# DAC_channel.net
KiCad netlist of a schematic drawn in Altium Designer
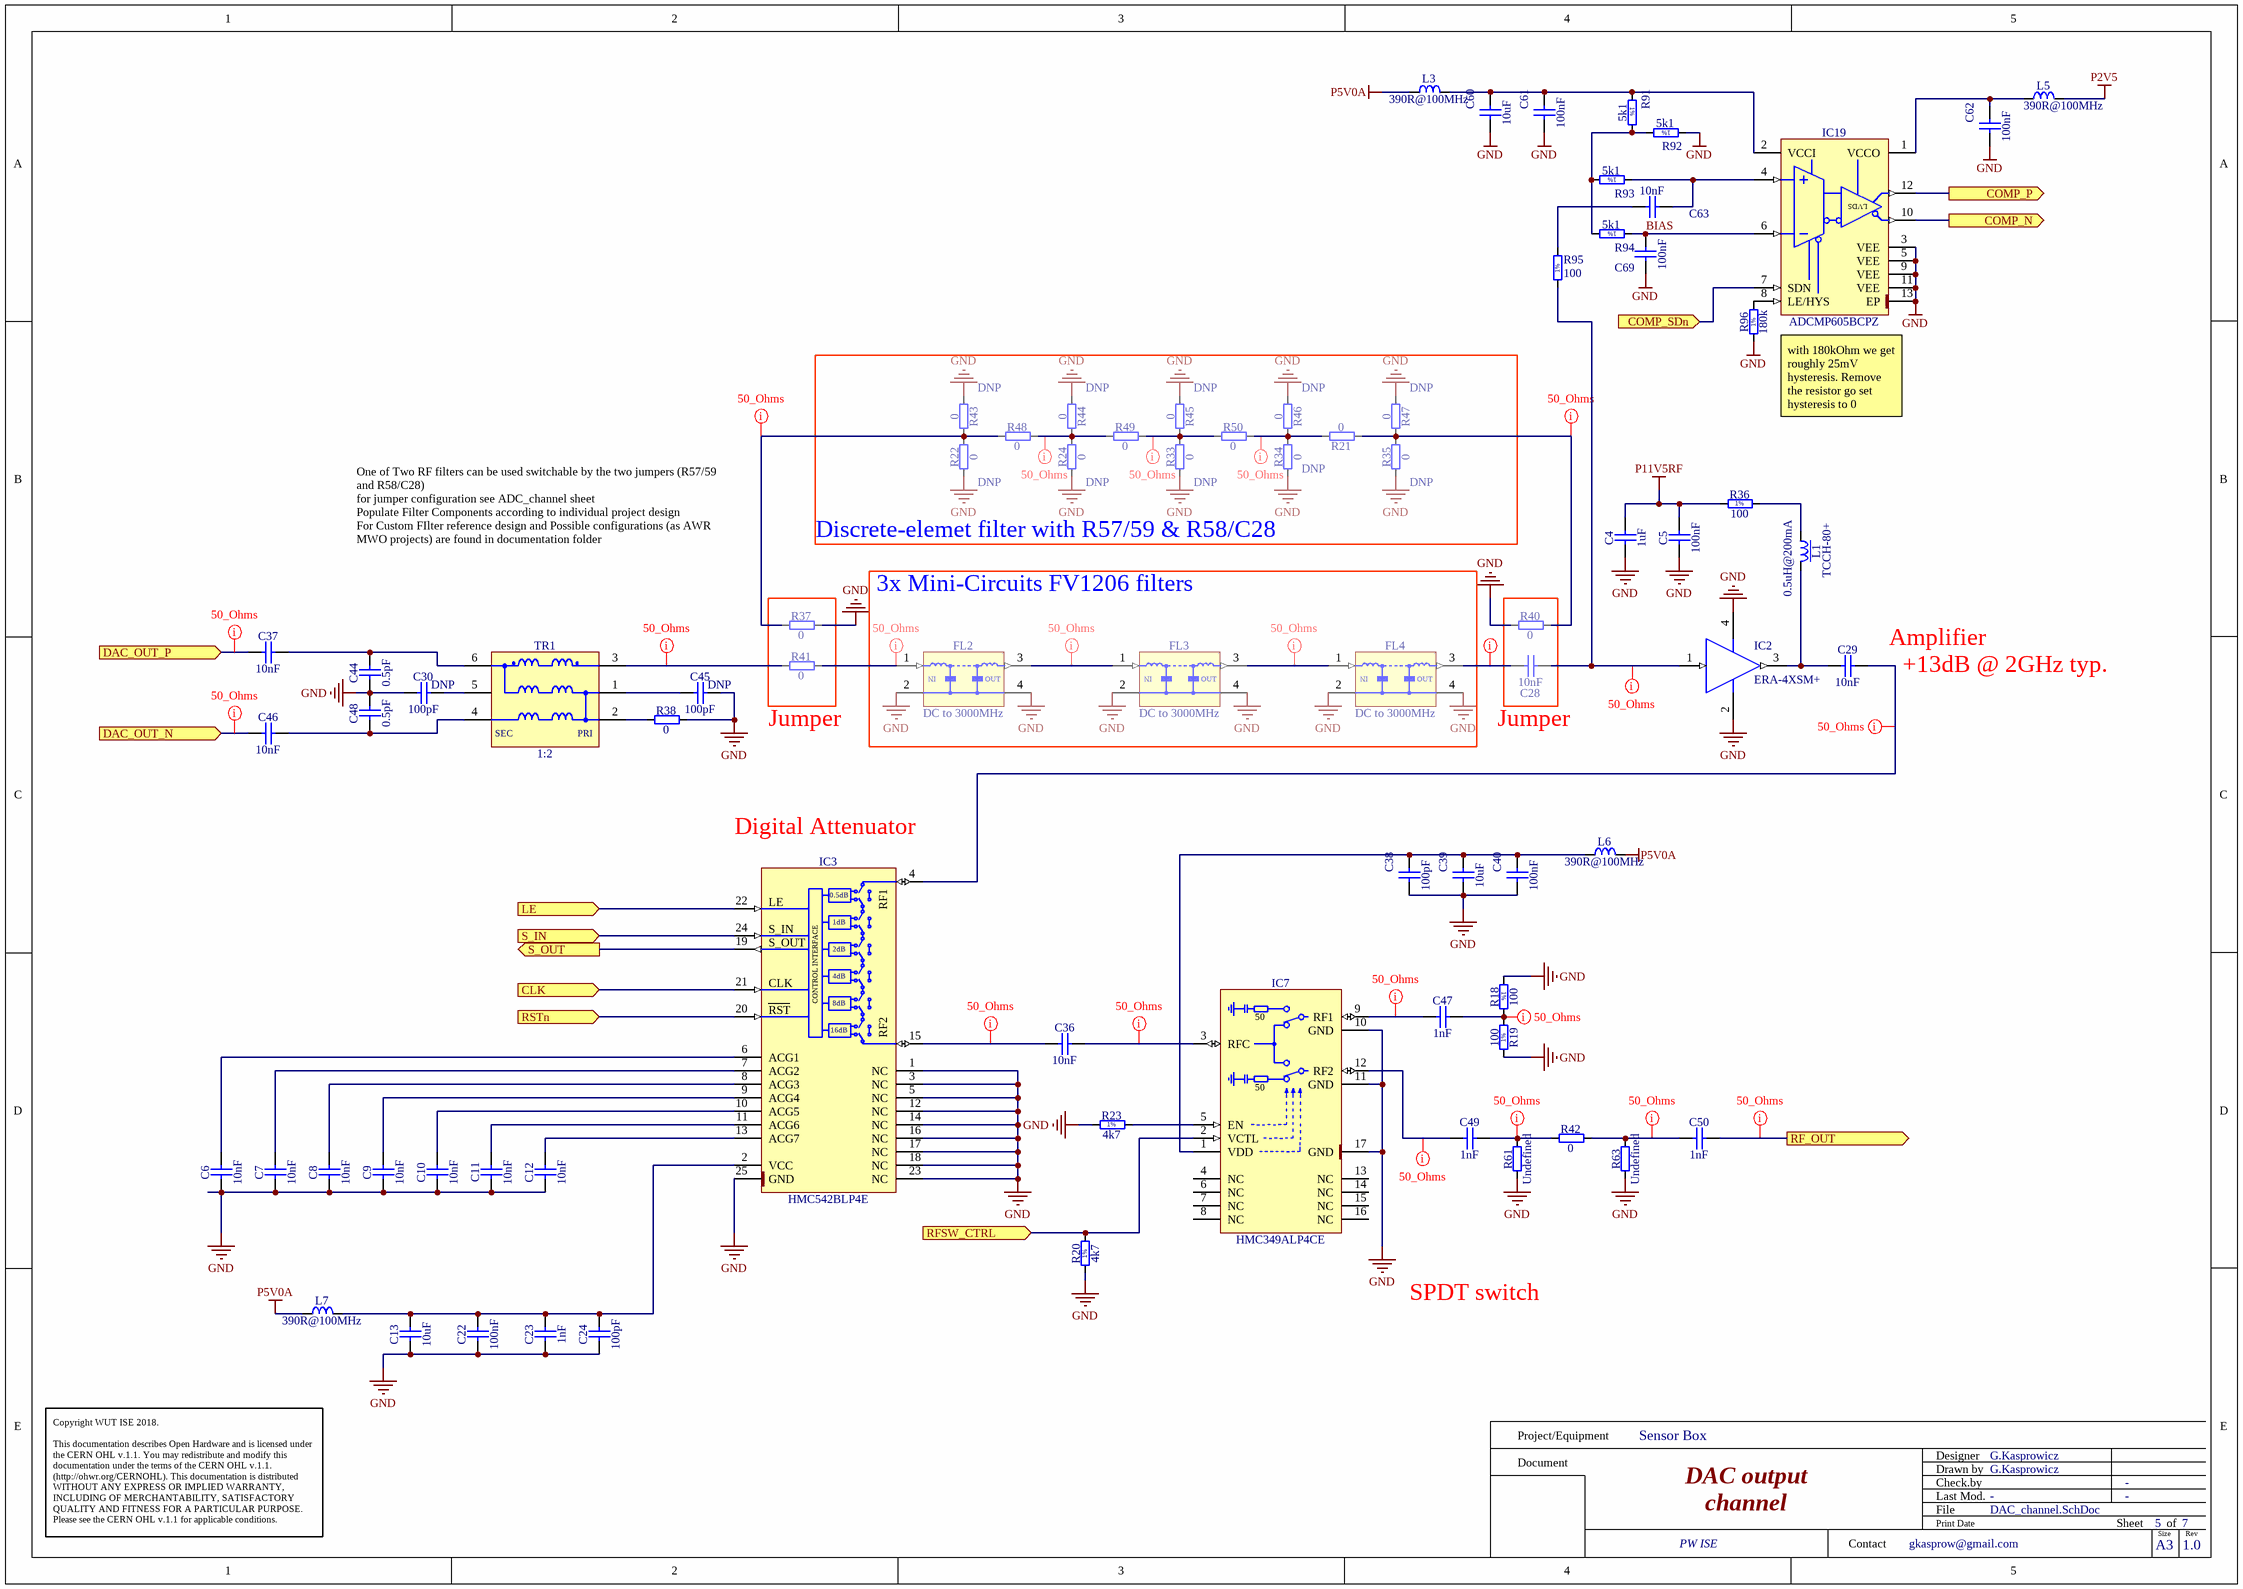
[diagram p0: DAC_channel.SchDoc]

(export (version "E")
  (design (tool "Eeschema 10.0.6"))
  (components
    (comp (ref "C4")
      (value "1uF")
      (footprint "CAPC2012X140N")
      (description "Non-polarised capacitor")
      (fields
        (field (name "PART NUMBER") "CC0805_1UF_35V_20%_X7R")
        (field (name "VOLTAGE") "35V")
        (field (name "AUTHOR") "CERN DEM JLC")
      )
      (libsource (lib "Capacitors") (part "Capacitor - non polarized"))
    )
    (comp (ref "C5")
      (value "100nF")
      (footprint "CAPC1608X87N")
      (description "Non-polarised capacitor")
      (fields
        (field (name "PART NUMBER") "CC0603_100NF_50V_10%_X7R")
        (field (name "VOLTAGE") "50V")
        (field (name "AUTHOR") "CERN DEM JLC")
      )
      (libsource (lib "Capacitors") (part "Capacitor - non polarized"))
    )
    (comp (ref "C6")
      (value "10nF")
      (footprint "CAPC1005X55N")
      (description "Non-polarised capacitor")
      (fields
        (field (name "PART NUMBER") "CC0402_10NF_16V_10%_X7R")
        (field (name "VOLTAGE") "16V")
        (field (name "AUTHOR") "CERN DEM JLC")
      )
      (libsource (lib "Capacitors") (part "Capacitor - non polarized"))
    )
    (comp (ref "C7")
      (value "10nF")
      (footprint "CAPC1005X55N")
      (description "Non-polarised capacitor")
      (fields
        (field (name "PART NUMBER") "CC0402_10NF_16V_10%_X7R")
        (field (name "VOLTAGE") "16V")
        (field (name "AUTHOR") "CERN DEM JLC")
      )
      (libsource (lib "Capacitors") (part "Capacitor - non polarized"))
    )
    (comp (ref "C8")
      (value "10nF")
      (footprint "CAPC1005X55N")
      (description "Non-polarised capacitor")
      (fields
        (field (name "PART NUMBER") "CC0402_10NF_16V_10%_X7R")
        (field (name "VOLTAGE") "16V")
        (field (name "AUTHOR") "CERN DEM JLC")
      )
      (libsource (lib "Capacitors") (part "Capacitor - non polarized"))
    )
    (comp (ref "C9")
      (value "10nF")
      (footprint "CAPC1005X55N")
      (description "Non-polarised capacitor")
      (fields
        (field (name "PART NUMBER") "CC0402_10NF_16V_10%_X7R")
        (field (name "VOLTAGE") "16V")
        (field (name "AUTHOR") "CERN DEM JLC")
      )
      (libsource (lib "Capacitors") (part "Capacitor - non polarized"))
    )
    (comp (ref "C10")
      (value "10nF")
      (footprint "CAPC1005X55N")
      (description "Non-polarised capacitor")
      (fields
        (field (name "PART NUMBER") "CC0402_10NF_16V_10%_X7R")
        (field (name "VOLTAGE") "16V")
        (field (name "AUTHOR") "CERN DEM JLC")
      )
      (libsource (lib "Capacitors") (part "Capacitor - non polarized"))
    )
    (comp (ref "C11")
      (value "10nF")
      (footprint "CAPC1005X55N")
      (description "Non-polarised capacitor")
      (fields
        (field (name "PART NUMBER") "CC0402_10NF_16V_10%_X7R")
        (field (name "VOLTAGE") "16V")
        (field (name "AUTHOR") "CERN DEM JLC")
      )
      (libsource (lib "Capacitors") (part "Capacitor - non polarized"))
    )
    (comp (ref "C12")
      (value "10nF")
      (footprint "CAPC1005X55N")
      (description "Non-polarised capacitor")
      (fields
        (field (name "PART NUMBER") "CC0402_10NF_16V_10%_X7R")
        (field (name "VOLTAGE") "16V")
        (field (name "AUTHOR") "CERN DEM JLC")
      )
      (libsource (lib "Capacitors") (part "Capacitor - non polarized"))
    )
    (comp (ref "C13")
      (value "10uF")
      (footprint "CAPC1608X80N")
      (description "Non-polarised capacitor")
      (fields
        (field (name "PART NUMBER") "CC0603_10UF_16V_20%_X5R")
        (field (name "VOLTAGE") "16V")
        (field (name "AUTHOR") "CERN DEM MR")
      )
      (libsource (lib "Capacitors") (part "Capacitor - non polarized"))
    )
    (comp (ref "C22")
      (value "100nF")
      (footprint "CAPC1005X55N")
      (description "Non-polarised capacitor")
      (fields
        (field (name "PART NUMBER") "CC0402_100NF_16V_10%_X7R")
        (field (name "VOLTAGE") "16V")
        (field (name "AUTHOR") "CERN DEM JLC")
      )
      (libsource (lib "Capacitors") (part "Capacitor - non polarized"))
    )
    (comp (ref "C23")
      (value "1nF")
      (footprint "CAPC1005X55N")
      (description "Non-polarised capacitor")
      (fields
        (field (name "PART NUMBER") "CC0402_1NF_50V_10%_X7R")
        (field (name "VOLTAGE") "50V")
        (field (name "AUTHOR") "CERN DEM JLC")
      )
      (libsource (lib "Capacitors") (part "Capacitor - non polarized"))
    )
    (comp (ref "C24")
      (value "100pF")
      (footprint "CAPC1005X55N")
      (description "Non-polarised capacitor")
      (fields
        (field (name "PART NUMBER") "CC0402_100PF_50V_5%_C0G")
        (field (name "VOLTAGE") "50V")
        (field (name "AUTHOR") "CERN DEM JLC")
      )
      (libsource (lib "Capacitors") (part "Capacitor - non polarized"))
    )
    (comp (ref "C28")
      (value "10nF")
      (footprint "CAPC1005X55N")
      (description "Non-polarised capacitor")
      (fields
        (field (name "PART NUMBER") "CC0402_10NF_16V_10%_X7R")
        (field (name "VOLTAGE") "16V")
        (field (name "AUTHOR") "CERN DEM JLC")
      )
      (libsource (lib "Capacitors") (part "Capacitor - non polarized"))
    )
    (comp (ref "C29")
      (value "10nF")
      (footprint "CAPC1005X55N")
      (description "Non-polarised capacitor")
      (fields
        (field (name "PART NUMBER") "CC0402_10NF_16V_10%_X7R")
        (field (name "VOLTAGE") "16V")
        (field (name "AUTHOR") "CERN DEM JLC")
      )
      (libsource (lib "Capacitors") (part "Capacitor - non polarized"))
    )
    (comp (ref "C30")
      (value "100pF")
      (footprint "CAPC1005X55N")
      (description "Non-polarised capacitor")
      (fields
        (field (name "PART NUMBER") "CC0402_100PF_50V_5%_C0G")
        (field (name "VOLTAGE") "50V")
        (field (name "MOUNTED") "DNP")
        (field (name "AUTHOR") "CERN DEM JLC")
      )
      (libsource (lib "Capacitors") (part "Capacitor - non polarized"))
    )
    (comp (ref "C36")
      (value "10nF")
      (footprint "CAPC1005X55N")
      (description "Non-polarised capacitor")
      (fields
        (field (name "PART NUMBER") "CC0402_10NF_16V_10%_X7R")
        (field (name "VOLTAGE") "16V")
        (field (name "AUTHOR") "CERN DEM JLC")
      )
      (libsource (lib "Capacitors") (part "Capacitor - non polarized"))
    )
    (comp (ref "C37")
      (value "10nF")
      (footprint "CAPC1005X55N")
      (description "Non-polarised capacitor")
      (fields
        (field (name "PART NUMBER") "CC0402_10NF_16V_10%_X7R")
        (field (name "VOLTAGE") "16V")
        (field (name "AUTHOR") "CERN DEM JLC")
      )
      (libsource (lib "Capacitors") (part "Capacitor - non polarized"))
    )
    (comp (ref "C38")
      (value "100pF")
      (footprint "CAPC1005X55N")
      (description "Non-polarised capacitor")
      (fields
        (field (name "PART NUMBER") "CC0402_100PF_50V_5%_C0G")
        (field (name "VOLTAGE") "50V")
        (field (name "AUTHOR") "CERN DEM JLC")
      )
      (libsource (lib "Capacitors") (part "Capacitor - non polarized"))
    )
    (comp (ref "C39")
      (value "10uF")
      (footprint "CAPC1608X80N")
      (description "Non-polarised capacitor")
      (fields
        (field (name "PART NUMBER") "CC0603_10UF_16V_20%_X5R")
        (field (name "VOLTAGE") "16V")
        (field (name "AUTHOR") "CERN DEM MR")
      )
      (libsource (lib "Capacitors") (part "Capacitor - non polarized"))
    )
    (comp (ref "C40")
      (value "100nF")
      (footprint "CAPC1005X55N")
      (description "Non-polarised capacitor")
      (fields
        (field (name "PART NUMBER") "CC0402_100NF_16V_10%_X7R")
        (field (name "VOLTAGE") "16V")
        (field (name "AUTHOR") "CERN DEM JLC")
      )
      (libsource (lib "Capacitors") (part "Capacitor - non polarized"))
    )
    (comp (ref "C44")
      (value "0.5pF")
      (footprint "CAPC1005X50N")
      (description "Non-polarised capacitor")
      (fields
        (field (name "PART NUMBER") "CC0402_0.5PF_25V_0.05PF_AVX_04023J0R5ABSTR")
        (field (name "VOLTAGE") "25V")
        (field (name "AUTHOR") "CERN DEM JLC")
      )
      (libsource (lib "Capacitors") (part "Capacitor - non polarized"))
    )
    (comp (ref "C45")
      (value "100pF")
      (footprint "CAPC1005X55N")
      (description "Non-polarised capacitor")
      (fields
        (field (name "PART NUMBER") "CC0402_100PF_50V_5%_C0G")
        (field (name "VOLTAGE") "50V")
        (field (name "MOUNTED") "DNP")
        (field (name "AUTHOR") "CERN DEM JLC")
      )
      (libsource (lib "Capacitors") (part "Capacitor - non polarized"))
    )
    (comp (ref "C46")
      (value "10nF")
      (footprint "CAPC1005X55N")
      (description "Non-polarised capacitor")
      (fields
        (field (name "PART NUMBER") "CC0402_10NF_16V_10%_X7R")
        (field (name "VOLTAGE") "16V")
        (field (name "AUTHOR") "CERN DEM JLC")
      )
      (libsource (lib "Capacitors") (part "Capacitor - non polarized"))
    )
    (comp (ref "C47")
      (value "1nF")
      (footprint "CAPC1005X55N")
      (description "Non-polarised capacitor")
      (fields
        (field (name "PART NUMBER") "CC0402_1NF_50V_10%_X7R")
        (field (name "VOLTAGE") "50V")
        (field (name "AUTHOR") "CERN DEM JLC")
      )
      (libsource (lib "Capacitors") (part "Capacitor - non polarized"))
    )
    (comp (ref "C48")
      (value "0.5pF")
      (footprint "CAPC1005X50N")
      (description "Non-polarised capacitor")
      (fields
        (field (name "PART NUMBER") "CC0402_0.5PF_25V_0.05PF_AVX_04023J0R5ABSTR")
        (field (name "VOLTAGE") "25V")
        (field (name "AUTHOR") "CERN DEM JLC")
      )
      (libsource (lib "Capacitors") (part "Capacitor - non polarized"))
    )
    (comp (ref "C49")
      (value "1nF")
      (footprint "CAPC1005X55N")
      (description "Non-polarised capacitor")
      (fields
        (field (name "PART NUMBER") "CC0402_1NF_50V_10%_X7R")
        (field (name "VOLTAGE") "50V")
        (field (name "AUTHOR") "CERN DEM JLC")
      )
      (libsource (lib "Capacitors") (part "Capacitor - non polarized"))
    )
    (comp (ref "C50")
      (value "1nF")
      (footprint "CAPC1005X55N")
      (description "Non-polarised capacitor")
      (fields
        (field (name "PART NUMBER") "CC0402_1NF_50V_10%_X7R")
        (field (name "VOLTAGE") "50V")
        (field (name "AUTHOR") "CERN DEM JLC")
      )
      (libsource (lib "Capacitors") (part "Capacitor - non polarized"))
    )
    (comp (ref "C60")
      (value "10uF")
      (footprint "CAPC1608X80N")
      (description "Non-polarised capacitor")
      (fields
        (field (name "PART NUMBER") "CC0603_10UF_16V_20%_X5R")
        (field (name "VOLTAGE") "16V")
        (field (name "AUTHOR") "CERN DEM MR")
      )
      (libsource (lib "Capacitors") (part "Capacitor - non polarized"))
    )
    (comp (ref "C61")
      (value "100nF")
      (footprint "CAPC1005X55N")
      (description "Non-polarised capacitor")
      (fields
        (field (name "PART NUMBER") "CC0402_100NF_16V_10%_X7R")
        (field (name "VOLTAGE") "16V")
        (field (name "AUTHOR") "CERN DEM JLC")
      )
      (libsource (lib "Capacitors") (part "Capacitor - non polarized"))
    )
    (comp (ref "C62")
      (value "100nF")
      (footprint "CAPC1005X55N")
      (description "Non-polarised capacitor")
      (fields
        (field (name "PART NUMBER") "CC0402_100NF_16V_10%_X7R")
        (field (name "VOLTAGE") "16V")
        (field (name "AUTHOR") "CERN DEM JLC")
      )
      (libsource (lib "Capacitors") (part "Capacitor - non polarized"))
    )
    (comp (ref "C63")
      (value "10nF")
      (footprint "CAPC1005X55N")
      (description "Non-polarised capacitor")
      (fields
        (field (name "PART NUMBER") "CC0402_10NF_16V_10%_X7R")
        (field (name "VOLTAGE") "16V")
        (field (name "AUTHOR") "CERN DEM JLC")
      )
      (libsource (lib "Capacitors") (part "Capacitor - non polarized"))
    )
    (comp (ref "C69")
      (value "100nF")
      (footprint "CAPC1005X55N")
      (description "Non-polarised capacitor")
      (fields
        (field (name "PART NUMBER") "CC0402_100NF_16V_10%_X7R")
        (field (name "VOLTAGE") "16V")
        (field (name "AUTHOR") "CERN DEM JLC")
      )
      (libsource (lib "Capacitors") (part "Capacitor - non polarized"))
    )
    (comp (ref "FL2")
      (value "DC to 3000MHz")
      (footprint "FIL_MINI-CIRCUITS_FV1206")
      (description "50 Ohm DC to 3000MHz Low Pass Filter")
      (fields
        (field (name "PART NUMBER") "FIL_MINI-CIRCUITS_LFCN-3000+")
        (field (name "MANUFACTURER") "MINI-CIRCUITS")
        (field (name "AUTHOR") "CERN DEM JLC")
      )
      (libsource (lib "Inductors & Transformers") (part "FIL_MINI-CIRCUITS_LFCN-3000+"))
    )
    (comp (ref "FL3")
      (value "DC to 3000MHz")
      (footprint "FIL_MINI-CIRCUITS_FV1206")
      (description "50 Ohm DC to 3000MHz Low Pass Filter")
      (fields
        (field (name "PART NUMBER") "FIL_MINI-CIRCUITS_LFCN-3000+")
        (field (name "MANUFACTURER") "MINI-CIRCUITS")
        (field (name "AUTHOR") "CERN DEM JLC")
      )
      (libsource (lib "Inductors & Transformers") (part "FIL_MINI-CIRCUITS_LFCN-3000+"))
    )
    (comp (ref "FL4")
      (value "DC to 3000MHz")
      (footprint "FIL_MINI-CIRCUITS_FV1206")
      (description "50 Ohm DC to 3000MHz Low Pass Filter")
      (fields
        (field (name "PART NUMBER") "FIL_MINI-CIRCUITS_LFCN-3000+")
        (field (name "MANUFACTURER") "MINI-CIRCUITS")
        (field (name "AUTHOR") "CERN DEM JLC")
      )
      (libsource (lib "Inductors & Transformers") (part "FIL_MINI-CIRCUITS_LFCN-3000+"))
    )
    (comp (ref "IC2")
      (value "ERA-4XSM+")
      (footprint "MINI-CIRCUITS_WW107")
      (description "DC-4GHz Monolithic Amplifier")
      (fields (field (name "MANUFACTURER") "MINI-CIRCUITS") (field (name "AUTHOR") "CERN DEM JMW"))
      (libsource (lib "ICs And Semiconductors") (part "ERA-4XSM+"))
    )
    (comp (ref "IC3")
      (value "HMC542BLP4E")
      (footprint "QFN50P400X400X100-25N-S295")
      (description "0.5dB LSB GaAs MMIC 6-bit Digital Serial Control Attenuator, DC - 4GHz")
      (fields (field (name "MANUFACTURER") "HITTITE MICROWAVE CORP") (field (name "AUTHOR") "CERN DEM JMW"))
      (libsource (lib "ICs And Semiconductors") (part "HMC542BLP4E"))
    )
    (comp (ref "IC7")
      (value "HMC349ALP4CE")
      (footprint "QFN65P400X400X100-17N-S255")
      (description "DC-4GHz High Isolation SPDT Non-Reflective Switch")
      (fields (field (name "MANUFACTURER") "ANALOG DEVICES") (field (name "AUTHOR") "CERN DEM JLC"))
      (libsource (lib "ICs And Semiconductors") (part "HMC349ALP4CE"))
    )
    (comp (ref "IC19")
      (value "ADCMP605BCPZ")
      (footprint "QFN50P300X300X100-13N-S145")
      (description "Rail-to-Rail, Very Fast, 2.5 V to 5.5 V Single-Supply LVDS Comparators")
      (fields (field (name "MANUFACTURER") "ANALOG DEVICES") (field (name "AUTHOR") "CERN DEM JLC"))
      (libsource (lib "ICs And Semiconductors") (part "ADCMP605BCPZ"))
    )
    (comp (ref "L1")
      (value "0.5uH@200mA")
      (footprint "IND_MINI-CIRCUITS_GU1604")
      (description "50 Ohms, 50 to 8200 MHz RF Choke")
      (fields
        (field (name "PART NUMBER") "IND_MINI-CIRCUITS_TCCH-80+")
        (field (name "POWER") "200mA")
        (field (name "MANUFACTURER PART NUMBER") "TCCH-80+")
        (field (name "AUTHOR") "CERN DEM JLC")
      )
      (libsource (lib "Inductors & Transformers") (part "IND_MINI-CIRCUITS_TCCH-80+"))
    )
    (comp (ref "L3")
      (value "390R@100MHz")
      (footprint "INDC1608X95N")
      (description "Inductor")
      (fields
        (field (name "PART NUMBER") "IND0603_TDK_MPZ1608R391A")
        (field (name "POWER") "1.2A")
        (field (name "AUTHOR") "CERN DEM JLC")
      )
      (libsource (lib "Inductors & Transformers") (part "Inductor"))
    )
    (comp (ref "L5")
      (value "390R@100MHz")
      (footprint "INDC1608X95N")
      (description "Inductor")
      (fields
        (field (name "PART NUMBER") "IND0603_TDK_MPZ1608R391A")
        (field (name "POWER") "1.2A")
        (field (name "AUTHOR") "CERN DEM JLC")
      )
      (libsource (lib "Inductors & Transformers") (part "Inductor"))
    )
    (comp (ref "L6")
      (value "390R@100MHz")
      (footprint "INDC1608X95N")
      (description "Inductor")
      (fields
        (field (name "PART NUMBER") "IND0603_TDK_MPZ1608R391A")
        (field (name "POWER") "1.2A")
        (field (name "AUTHOR") "CERN DEM JLC")
      )
      (libsource (lib "Inductors & Transformers") (part "Inductor"))
    )
    (comp (ref "L7")
      (value "390R@100MHz")
      (footprint "INDC1608X95N")
      (description "Inductor")
      (fields
        (field (name "PART NUMBER") "IND0603_TDK_MPZ1608R391A")
        (field (name "POWER") "1.2A")
        (field (name "AUTHOR") "CERN DEM JLC")
      )
      (libsource (lib "Inductors & Transformers") (part "Inductor"))
    )
    (comp (ref "R18")
      (value "100")
      (footprint "RESC1005X40N")
      (description "Resistor - 1%")
      (fields
        (field (name "PART NUMBER") "R0402_100R_1%_0.0625W_100PPM")
        (field (name "POWER") "0.0625W")
        (field (name "AUTHOR") "CERN DEM JLC")
      )
      (libsource (lib "Resistors") (part "Resistor - 1%"))
    )
    (comp (ref "R19")
      (value "100")
      (footprint "RESC1005X40N")
      (description "Resistor - 1%")
      (fields
        (field (name "PART NUMBER") "R0402_100R_1%_0.0625W_100PPM")
        (field (name "POWER") "0.0625W")
        (field (name "AUTHOR") "CERN DEM JLC")
      )
      (libsource (lib "Resistors") (part "Resistor - 1%"))
    )
    (comp (ref "R20")
      (value "4k7")
      (footprint "RESC1005X40N")
      (description "Resistor - 1%")
      (fields
        (field (name "PART NUMBER") "R0402_4K7_1%_0.0625W_100PPM")
        (field (name "POWER") "0.0625W")
        (field (name "AUTHOR") "CERN DEM JLC")
      )
      (libsource (lib "Resistors") (part "Resistor - 1%"))
    )
    (comp (ref "R21")
      (value "0")
      (footprint "RESC1005X40N")
      (description "Resistor")
      (fields
        (field (name "PART NUMBER") "R0402_0R_JUMPER")
        (field (name "MANUFACTURER") "GENERIC")
        (field (name "AUTHOR") "CERN DEM JLC")
      )
      (libsource (lib "Resistors") (part "Resistor"))
    )
    (comp (ref "R22")
      (value "0")
      (footprint "RESC1005X40N")
      (description "Resistor")
      (fields
        (field (name "PART NUMBER") "R0402_0R_JUMPER")
        (field (name "MANUFACTURER") "GENERIC")
        (field (name "MOUNTED") "DNP")
        (field (name "AUTHOR") "CERN DEM JLC")
      )
      (libsource (lib "Resistors") (part "Resistor"))
    )
    (comp (ref "R23")
      (value "4k7")
      (footprint "RESC1005X40N")
      (description "Resistor - 1%")
      (fields
        (field (name "PART NUMBER") "R0402_4K7_1%_0.0625W_100PPM")
        (field (name "POWER") "0.0625W")
        (field (name "AUTHOR") "CERN DEM JLC")
      )
      (libsource (lib "Resistors") (part "Resistor - 1%"))
    )
    (comp (ref "R24")
      (value "0")
      (footprint "RESC1005X40N")
      (description "Resistor")
      (fields
        (field (name "PART NUMBER") "R0402_0R_JUMPER")
        (field (name "MANUFACTURER") "GENERIC")
        (field (name "MOUNTED") "DNP")
        (field (name "AUTHOR") "CERN DEM JLC")
      )
      (libsource (lib "Resistors") (part "Resistor"))
    )
    (comp (ref "R33")
      (value "0")
      (footprint "RESC1005X40N")
      (description "Resistor")
      (fields
        (field (name "PART NUMBER") "R0402_0R_JUMPER")
        (field (name "MANUFACTURER") "GENERIC")
        (field (name "MOUNTED") "DNP")
        (field (name "AUTHOR") "CERN DEM JLC")
      )
      (libsource (lib "Resistors") (part "Resistor"))
    )
    (comp (ref "R34")
      (value "0")
      (footprint "RESC1005X40N")
      (description "Resistor")
      (fields
        (field (name "PART NUMBER") "R0402_0R_JUMPER")
        (field (name "MANUFACTURER") "GENERIC")
        (field (name "MOUNTED") "DNP")
        (field (name "AUTHOR") "CERN DEM JLC")
      )
      (libsource (lib "Resistors") (part "Resistor"))
    )
    (comp (ref "R35")
      (value "0")
      (footprint "RESC1005X40N")
      (description "Resistor")
      (fields
        (field (name "PART NUMBER") "R0402_0R_JUMPER")
        (field (name "MANUFACTURER") "GENERIC")
        (field (name "MOUNTED") "DNP")
        (field (name "AUTHOR") "CERN DEM JLC")
      )
      (libsource (lib "Resistors") (part "Resistor"))
    )
    (comp (ref "R36")
      (value "100")
      (footprint "RESC3146X65N")
      (description "Resistor - 1%")
      (fields
        (field (name "PART NUMBER") "R1218_100R_1%_1W_100PPM")
        (field (name "POWER") "1W")
        (field (name "AUTHOR") "CERN DEM JLC")
      )
      (libsource (lib "Resistors") (part "Resistor - 1%"))
    )
    (comp (ref "R37")
      (value "0")
      (footprint "RESC1005X40N")
      (description "Resistor")
      (fields
        (field (name "PART NUMBER") "R0402_0R_JUMPER")
        (field (name "MANUFACTURER") "GENERIC")
        (field (name "AUTHOR") "CERN DEM JLC")
      )
      (libsource (lib "Resistors") (part "Resistor"))
    )
    (comp (ref "R38")
      (value "0")
      (footprint "RESC1005X40N")
      (description "Resistor")
      (fields
        (field (name "PART NUMBER") "R0402_0R_JUMPER")
        (field (name "MANUFACTURER") "GENERIC")
        (field (name "AUTHOR") "CERN DEM JLC")
      )
      (libsource (lib "Resistors") (part "Resistor"))
    )
    (comp (ref "R40")
      (value "0")
      (footprint "RESC1005X40N")
      (description "Resistor")
      (fields
        (field (name "PART NUMBER") "R0402_0R_JUMPER")
        (field (name "MANUFACTURER") "GENERIC")
        (field (name "AUTHOR") "CERN DEM JLC")
      )
      (libsource (lib "Resistors") (part "Resistor"))
    )
    (comp (ref "R41")
      (value "0")
      (footprint "RESC1005X40N")
      (description "Resistor")
      (fields
        (field (name "PART NUMBER") "R0402_0R_JUMPER")
        (field (name "MANUFACTURER") "GENERIC")
        (field (name "AUTHOR") "CERN DEM JLC")
      )
      (libsource (lib "Resistors") (part "Resistor"))
    )
    (comp (ref "R42")
      (value "0")
      (footprint "RESC1608X55N")
      (description "Resistor")
      (fields
        (field (name "PART NUMBER") "R0603_0R_JUMPER")
        (field (name "MANUFACTURER") "GENERIC")
        (field (name "AUTHOR") "CERN DEM JLC")
      )
      (libsource (lib "Resistors") (part "Resistor"))
    )
    (comp (ref "R43")
      (value "0")
      (footprint "RESC1005X40N")
      (description "Resistor")
      (fields
        (field (name "PART NUMBER") "R0402_0R_JUMPER")
        (field (name "MANUFACTURER") "GENERIC")
        (field (name "MOUNTED") "DNP")
        (field (name "AUTHOR") "CERN DEM JLC")
      )
      (libsource (lib "Resistors") (part "Resistor"))
    )
    (comp (ref "R44")
      (value "0")
      (footprint "RESC1005X40N")
      (description "Resistor")
      (fields
        (field (name "PART NUMBER") "R0402_0R_JUMPER")
        (field (name "MANUFACTURER") "GENERIC")
        (field (name "MOUNTED") "DNP")
        (field (name "AUTHOR") "CERN DEM JLC")
      )
      (libsource (lib "Resistors") (part "Resistor"))
    )
    (comp (ref "R45")
      (value "0")
      (footprint "RESC1005X40N")
      (description "Resistor")
      (fields
        (field (name "PART NUMBER") "R0402_0R_JUMPER")
        (field (name "MANUFACTURER") "GENERIC")
        (field (name "MOUNTED") "DNP")
        (field (name "AUTHOR") "CERN DEM JLC")
      )
      (libsource (lib "Resistors") (part "Resistor"))
    )
    (comp (ref "R46")
      (value "0")
      (footprint "RESC1005X40N")
      (description "Resistor")
      (fields
        (field (name "PART NUMBER") "R0402_0R_JUMPER")
        (field (name "MANUFACTURER") "GENERIC")
        (field (name "MOUNTED") "DNP")
        (field (name "AUTHOR") "CERN DEM JLC")
      )
      (libsource (lib "Resistors") (part "Resistor"))
    )
    (comp (ref "R47")
      (value "0")
      (footprint "RESC1005X40N")
      (description "Resistor")
      (fields
        (field (name "PART NUMBER") "R0402_0R_JUMPER")
        (field (name "MANUFACTURER") "GENERIC")
        (field (name "MOUNTED") "DNP")
        (field (name "AUTHOR") "CERN DEM JLC")
      )
      (libsource (lib "Resistors") (part "Resistor"))
    )
    (comp (ref "R48")
      (value "0")
      (footprint "RESC1005X40N")
      (description "Resistor")
      (fields
        (field (name "PART NUMBER") "R0402_0R_JUMPER")
        (field (name "MANUFACTURER") "GENERIC")
        (field (name "AUTHOR") "CERN DEM JLC")
      )
      (libsource (lib "Resistors") (part "Resistor"))
    )
    (comp (ref "R49")
      (value "0")
      (footprint "RESC1005X40N")
      (description "Resistor")
      (fields
        (field (name "PART NUMBER") "R0402_0R_JUMPER")
        (field (name "MANUFACTURER") "GENERIC")
        (field (name "AUTHOR") "CERN DEM JLC")
      )
      (libsource (lib "Resistors") (part "Resistor"))
    )
    (comp (ref "R50")
      (value "0")
      (footprint "RESC1005X40N")
      (description "Resistor")
      (fields
        (field (name "PART NUMBER") "R0402_0R_JUMPER")
        (field (name "MANUFACTURER") "GENERIC")
        (field (name "AUTHOR") "CERN DEM JLC")
      )
      (libsource (lib "Resistors") (part "Resistor"))
    )
    (comp (ref "R61")
      (value "Undefined")
      (footprint "RESC1608X55N")
      (description "Resistor")
      (fields (field (name "PART NUMBER") "R0603_NO-VALUE") (field (name "AUTHOR") "CERN DEM JLC"))
      (libsource (lib "Resistors") (part "Resistor"))
    )
    (comp (ref "R63")
      (value "Undefined")
      (footprint "RESC1608X55N")
      (description "Resistor")
      (fields (field (name "PART NUMBER") "R0603_NO-VALUE") (field (name "AUTHOR") "CERN DEM JLC"))
      (libsource (lib "Resistors") (part "Resistor"))
    )
    (comp (ref "R91")
      (value "5k1")
      (footprint "RESC1005X40N")
      (description "Resistor - 1%")
      (fields
        (field (name "PART NUMBER") "R0402_5K1_1%_0.0625W_100PPM")
        (field (name "POWER") "0.0625W")
        (field (name "AUTHOR") "CERN DEM JLC")
      )
      (libsource (lib "Resistors") (part "Resistor - 1%"))
    )
    (comp (ref "R92")
      (value "5k1")
      (footprint "RESC1005X40N")
      (description "Resistor - 1%")
      (fields
        (field (name "PART NUMBER") "R0402_5K1_1%_0.0625W_100PPM")
        (field (name "POWER") "0.0625W")
        (field (name "AUTHOR") "CERN DEM JLC")
      )
      (libsource (lib "Resistors") (part "Resistor - 1%"))
    )
    (comp (ref "R93")
      (value "5k1")
      (footprint "RESC1005X40N")
      (description "Resistor - 1%")
      (fields
        (field (name "PART NUMBER") "R0402_5K1_1%_0.0625W_100PPM")
        (field (name "POWER") "0.0625W")
        (field (name "AUTHOR") "CERN DEM JLC")
      )
      (libsource (lib "Resistors") (part "Resistor - 1%"))
    )
    (comp (ref "R94")
      (value "5k1")
      (footprint "RESC1005X40N")
      (description "Resistor - 1%")
      (fields
        (field (name "PART NUMBER") "R0402_5K1_1%_0.0625W_100PPM")
        (field (name "POWER") "0.0625W")
        (field (name "AUTHOR") "CERN DEM JLC")
      )
      (libsource (lib "Resistors") (part "Resistor - 1%"))
    )
    (comp (ref "R95")
      (value "100")
      (footprint "RESC1005X40N")
      (description "Resistor - 1%")
      (fields
        (field (name "PART NUMBER") "R0402_100R_1%_0.1W_100PPM")
        (field (name "POWER") "0.1W")
        (field (name "AUTHOR") "CERN DEM JLC")
      )
      (libsource (lib "Resistors") (part "Resistor - 1%"))
    )
    (comp (ref "R96")
      (value "180k")
      (footprint "RESC1005X40N")
      (description "Resistor - 1%")
      (fields
        (field (name "PART NUMBER") "R0402_180K_1%_0.0625W_100PPM")
        (field (name "POWER") "0.0625W")
        (field (name "AUTHOR") "CERN DEM JLC")
      )
      (libsource (lib "Resistors") (part "Resistor - 1%"))
    )
    (comp (ref "TR1")
      (value "1:2")
      (footprint "XFMR_MINI-CIRCUITS_DB1627")
      (description "50 OHMS 10 to 4000 MHz RF Transformer")
      (fields
        (field (name "PART NUMBER") "XFMR_MINI-CIRCUITS_TCM2-43X+")
        (field (name "POWER") "0.4W")
        (field (name "AUTHOR") "CERN DEM BC")
      )
      (libsource (lib "Inductors & Transformers") (part "XFMR_MINI-CIRCUITS_TCM2-43X"))
    )
  )
  (nets
    (net (code "1") (name "/BIAS") (class "Default")
      (node (ref "C69") (pin "2") (pinfunction "2_2") (pintype "passive"))
      (node (ref "IC19") (pin "6") (pinfunction "VN_6") (pintype "input"))
      (node (ref "R94") (pin "1") (pinfunction "1_1") (pintype "passive"))
    )
    (net (code "2") (name "/CLK") (class "Default")
      (node (ref "IC3") (pin "21") (pinfunction "SHIFT_CLOCK_21") (pintype "input"))
    )
    (net (code "3") (name "/COMP_N") (class "Default")
      (node (ref "IC19") (pin "10") (pinfunction "~{Q}_10") (pintype "output"))
    )
    (net (code "4") (name "/COMP_P") (class "Default")
      (node (ref "IC19") (pin "12") (pinfunction "Q_12") (pintype "output"))
    )
    (net (code "5") (name "/COMP_SDn") (class "Default")
      (node (ref "IC19") (pin "7") (pinfunction "SDN_7") (pintype "input"))
    )
    (net (code "6") (name "/DAC_OUT_N") (class "Default")
      (node (ref "C46") (pin "1") (pinfunction "1_1") (pintype "passive"))
    )
    (net (code "7") (name "/DAC_OUT_P") (class "Default")
      (node (ref "C37") (pin "1") (pinfunction "1_1") (pintype "passive"))
    )
    (net (code "8") (name "/LE") (class "Default")
      (node (ref "IC3") (pin "22") (pinfunction "LATCH_ENABLE_22") (pintype "input"))
    )
    (net (code "9") (name "/RFSW_CTRL") (class "Default")
      (node (ref "IC7") (pin "2") (pinfunction "VCTL_2") (pintype "input"))
      (node (ref "R20") (pin "2") (pinfunction "2_2") (pintype "passive"))
    )
    (net (code "10") (name "/RF_OUT") (class "Default")
      (node (ref "C50") (pin "2") (pinfunction "2_2") (pintype "passive"))
    )
    (net (code "11") (name "/RSTn") (class "Default")
      (node (ref "IC3") (pin "20") (pinfunction "~{RESET}_20") (pintype "input"))
    )
    (net (code "12") (name "/S_IN") (class "Default")
      (node (ref "IC3") (pin "24") (pinfunction "SERIAL_INPUT_24") (pintype "input"))
    )
    (net (code "13") (name "/S_OUT") (class "Default")
      (node (ref "IC3") (pin "19") (pinfunction "SERIAL_OUTPUT_19") (pintype "output"))
    )
    (net (code "14") (name "GND") (class "Default")
      (node (ref "C10") (pin "1") (pinfunction "1_1") (pintype "passive"))
      (node (ref "C11") (pin "1") (pinfunction "1_1") (pintype "passive"))
      (node (ref "C12") (pin "1") (pinfunction "1_1") (pintype "passive"))
      (node (ref "C13") (pin "1") (pinfunction "1_1") (pintype "passive"))
      (node (ref "C22") (pin "1") (pinfunction "1_1") (pintype "passive"))
      (node (ref "C23") (pin "1") (pinfunction "1_1") (pintype "passive"))
      (node (ref "C24") (pin "1") (pinfunction "1_1") (pintype "passive"))
      (node (ref "C30") (pin "1") (pinfunction "1_1") (pintype "passive"))
      (node (ref "C38") (pin "2") (pinfunction "2_2") (pintype "passive"))
      (node (ref "C39") (pin "1") (pinfunction "1_1") (pintype "passive"))
      (node (ref "C4") (pin "1") (pinfunction "1_1") (pintype "passive"))
      (node (ref "C40") (pin "1") (pinfunction "1_1") (pintype "passive"))
      (node (ref "C44") (pin "1") (pinfunction "1_1") (pintype "passive"))
      (node (ref "C45") (pin "2") (pinfunction "2_2") (pintype "passive"))
      (node (ref "C48") (pin "2") (pinfunction "2_2") (pintype "passive"))
      (node (ref "C5") (pin "1") (pinfunction "1_1") (pintype "passive"))
      (node (ref "C6") (pin "1") (pinfunction "1_1") (pintype "passive"))
      (node (ref "C60") (pin "1") (pinfunction "1_1") (pintype "passive"))
      (node (ref "C61") (pin "1") (pinfunction "1_1") (pintype "passive"))
      (node (ref "C62") (pin "1") (pinfunction "1_1") (pintype "passive"))
      (node (ref "C69") (pin "1") (pinfunction "1_1") (pintype "passive"))
      (node (ref "C7") (pin "1") (pinfunction "1_1") (pintype "passive"))
      (node (ref "C8") (pin "1") (pinfunction "1_1") (pintype "passive"))
      (node (ref "C9") (pin "1") (pinfunction "1_1") (pintype "passive"))
      (node (ref "FL2") (pin "2") (pinfunction "GND_2") (pintype "power_in"))
      (node (ref "FL2") (pin "4") (pinfunction "GND_4") (pintype "power_in"))
      (node (ref "FL3") (pin "2") (pinfunction "GND_2") (pintype "power_in"))
      (node (ref "FL3") (pin "4") (pinfunction "GND_4") (pintype "power_in"))
      (node (ref "FL4") (pin "2") (pinfunction "GND_2") (pintype "power_in"))
      (node (ref "FL4") (pin "4") (pinfunction "GND_4") (pintype "power_in"))
      (node (ref "IC19") (pin "11") (pinfunction "VEE_11") (pintype "power_in"))
      (node (ref "IC19") (pin "13") (pinfunction "EP_13") (pintype "power_in"))
      (node (ref "IC19") (pin "3") (pinfunction "VEE_3") (pintype "power_in"))
      (node (ref "IC19") (pin "5") (pinfunction "VEE_5") (pintype "power_in"))
      (node (ref "IC19") (pin "9") (pinfunction "VEE_9") (pintype "power_in"))
      (node (ref "IC2") (pin "2") (pinfunction "GND_2") (pintype "power_in"))
      (node (ref "IC2") (pin "4") (pinfunction "GND_4") (pintype "power_in"))
      (node (ref "IC3") (pin "1") (pinfunction "NC_1") (pintype "passive"))
      (node (ref "IC3") (pin "12") (pinfunction "NC_12") (pintype "passive"))
      (node (ref "IC3") (pin "14") (pinfunction "NC_14") (pintype "passive"))
      (node (ref "IC3") (pin "16") (pinfunction "NC_16") (pintype "passive"))
      (node (ref "IC3") (pin "17") (pinfunction "NC_17") (pintype "passive"))
      (node (ref "IC3") (pin "18") (pinfunction "NC_18") (pintype "passive"))
      (node (ref "IC3") (pin "23") (pinfunction "NC_23") (pintype "passive"))
      (node (ref "IC3") (pin "25") (pinfunction "GND_25") (pintype "power_in"))
      (node (ref "IC3") (pin "3") (pinfunction "NC_3") (pintype "passive"))
      (node (ref "IC3") (pin "5") (pinfunction "NC_5") (pintype "passive"))
      (node (ref "IC7") (pin "10") (pinfunction "GND_10") (pintype "power_in"))
      (node (ref "IC7") (pin "11") (pinfunction "GND_11") (pintype "power_in"))
      (node (ref "IC7") (pin "17") (pinfunction "GND_17") (pintype "power_in"))
      (node (ref "R18") (pin "1") (pinfunction "1_1") (pintype "passive"))
      (node (ref "R19") (pin "1") (pinfunction "1_1") (pintype "passive"))
      (node (ref "R20") (pin "1") (pinfunction "1_1") (pintype "passive"))
      (node (ref "R22") (pin "1") (pinfunction "1_1") (pintype "passive"))
      (node (ref "R23") (pin "1") (pinfunction "1_1") (pintype "passive"))
      (node (ref "R24") (pin "1") (pinfunction "1_1") (pintype "passive"))
      (node (ref "R33") (pin "1") (pinfunction "1_1") (pintype "passive"))
      (node (ref "R34") (pin "1") (pinfunction "1_1") (pintype "passive"))
      (node (ref "R35") (pin "1") (pinfunction "1_1") (pintype "passive"))
      (node (ref "R37") (pin "2") (pinfunction "2_2") (pintype "passive"))
      (node (ref "R38") (pin "2") (pinfunction "2_2") (pintype "passive"))
      (node (ref "R40") (pin "2") (pinfunction "2_2") (pintype "passive"))
      (node (ref "R43") (pin "1") (pinfunction "1_1") (pintype "passive"))
      (node (ref "R44") (pin "1") (pinfunction "1_1") (pintype "passive"))
      (node (ref "R45") (pin "1") (pinfunction "1_1") (pintype "passive"))
      (node (ref "R46") (pin "1") (pinfunction "1_1") (pintype "passive"))
      (node (ref "R47") (pin "1") (pinfunction "1_1") (pintype "passive"))
      (node (ref "R61") (pin "1") (pinfunction "1_1") (pintype "passive"))
      (node (ref "R63") (pin "1") (pinfunction "1_1") (pintype "passive"))
      (node (ref "R92") (pin "1") (pinfunction "1_1") (pintype "passive"))
      (node (ref "R96") (pin "1") (pinfunction "1_1") (pintype "passive"))
    )
    (net (code "15") (name "Net-(C37-Pad2)") (class "Default")
      (node (ref "C37") (pin "2") (pinfunction "2_2") (pintype "passive"))
      (node (ref "C44") (pin "2") (pinfunction "2_2") (pintype "passive"))
      (node (ref "TR1") (pin "6") (pinfunction "S1_6") (pintype "passive"))
    )
    (net (code "16") (name "Net-(C45-Pad1)") (class "Default")
      (node (ref "C45") (pin "1") (pinfunction "1_1") (pintype "passive"))
      (node (ref "TR1") (pin "1") (pinfunction "P1_1") (pintype "passive"))
    )
    (net (code "17") (name "Net-(C46-Pad2)") (class "Default")
      (node (ref "C46") (pin "2") (pinfunction "2_2") (pintype "passive"))
      (node (ref "C48") (pin "1") (pinfunction "1_1") (pintype "passive"))
      (node (ref "TR1") (pin "4") (pinfunction "S1_4") (pintype "passive"))
    )
    (net (code "18") (name "Net-(C47-Pad2)") (class "Default")
      (node (ref "C47") (pin "2") (pinfunction "2_2") (pintype "passive"))
      (node (ref "R18") (pin "2") (pinfunction "2_2") (pintype "passive"))
      (node (ref "R19") (pin "2") (pinfunction "2_2") (pintype "passive"))
    )
    (net (code "19") (name "Net-(C49-Pad2)") (class "Default")
      (node (ref "C49") (pin "2") (pinfunction "2_2") (pintype "passive"))
      (node (ref "R42") (pin "1") (pinfunction "1_1") (pintype "passive"))
      (node (ref "R61") (pin "2") (pinfunction "2_2") (pintype "passive"))
    )
    (net (code "20") (name "Net-(C50-Pad1)") (class "Default")
      (node (ref "C50") (pin "1") (pinfunction "1_1") (pintype "passive"))
      (node (ref "R42") (pin "2") (pinfunction "2_2") (pintype "passive"))
      (node (ref "R63") (pin "2") (pinfunction "2_2") (pintype "passive"))
    )
    (net (code "21") (name "Net-(C63-Pad2)") (class "Default")
      (node (ref "C63") (pin "2") (pinfunction "2_2") (pintype "passive"))
      (node (ref "R95") (pin "2") (pinfunction "2_2") (pintype "passive"))
    )
    (net (code "22") (name "Net-(FL2-RFIN)") (class "Default")
      (node (ref "FL2") (pin "1") (pinfunction "RFIN_1") (pintype "input"))
      (node (ref "R41") (pin "2") (pinfunction "2_2") (pintype "passive"))
    )
    (net (code "23") (name "Net-(FL2-RFOUT)") (class "Default")
      (node (ref "FL2") (pin "3") (pinfunction "RFOUT_3") (pintype "output"))
      (node (ref "FL3") (pin "1") (pinfunction "RFIN_1") (pintype "input"))
    )
    (net (code "24") (name "Net-(FL3-RFOUT)") (class "Default")
      (node (ref "FL3") (pin "3") (pinfunction "RFOUT_3") (pintype "output"))
      (node (ref "FL4") (pin "1") (pinfunction "RFIN_1") (pintype "input"))
    )
    (net (code "25") (name "Net-(FL4-RFOUT)") (class "Default")
      (node (ref "C28") (pin "1") (pinfunction "1_1") (pintype "passive"))
      (node (ref "FL4") (pin "3") (pinfunction "RFOUT_3") (pintype "output"))
    )
    (net (code "26") (name "Net-(IC2-RF_IN)") (class "Default")
      (node (ref "C28") (pin "2") (pinfunction "2_2") (pintype "passive"))
      (node (ref "IC2") (pin "1") (pinfunction "RF_IN_1") (pintype "input"))
      (node (ref "R95") (pin "1") (pinfunction "1_1") (pintype "passive"))
    )
    (net (code "27") (name "Net-(IC2-RF_OUT)") (class "Default")
      (node (ref "C29") (pin "1") (pinfunction "1_1") (pintype "passive"))
      (node (ref "IC2") (pin "3") (pinfunction "RF_OUT_3") (pintype "output"))
      (node (ref "L1") (pin "3") (pinfunction "3_3") (pintype "passive"))
    )
    (net (code "28") (name "Net-(IC3-ACG1)") (class "Default")
      (node (ref "C6") (pin "2") (pinfunction "2_2") (pintype "passive"))
      (node (ref "IC3") (pin "6") (pinfunction "ACG1_6") (pintype "passive"))
    )
    (net (code "29") (name "Net-(IC3-ACG2)") (class "Default")
      (node (ref "C7") (pin "2") (pinfunction "2_2") (pintype "passive"))
      (node (ref "IC3") (pin "7") (pinfunction "ACG2_7") (pintype "passive"))
    )
    (net (code "30") (name "Net-(IC3-ACG3)") (class "Default")
      (node (ref "C8") (pin "2") (pinfunction "2_2") (pintype "passive"))
      (node (ref "IC3") (pin "8") (pinfunction "ACG3_8") (pintype "passive"))
    )
    (net (code "31") (name "Net-(IC3-ACG4)") (class "Default")
      (node (ref "C9") (pin "2") (pinfunction "2_2") (pintype "passive"))
      (node (ref "IC3") (pin "9") (pinfunction "ACG4_9") (pintype "passive"))
    )
    (net (code "32") (name "Net-(IC3-ACG5)") (class "Default")
      (node (ref "C10") (pin "2") (pinfunction "2_2") (pintype "passive"))
      (node (ref "IC3") (pin "10") (pinfunction "ACG5_10") (pintype "passive"))
    )
    (net (code "33") (name "Net-(IC3-ACG6)") (class "Default")
      (node (ref "C11") (pin "2") (pinfunction "2_2") (pintype "passive"))
      (node (ref "IC3") (pin "11") (pinfunction "ACG6_11") (pintype "passive"))
    )
    (net (code "34") (name "Net-(IC3-ACG7)") (class "Default")
      (node (ref "C12") (pin "2") (pinfunction "2_2") (pintype "passive"))
      (node (ref "IC3") (pin "13") (pinfunction "ACG7_13") (pintype "passive"))
    )
    (net (code "35") (name "Net-(IC3-RF1)") (class "Default")
      (node (ref "C29") (pin "2") (pinfunction "2_2") (pintype "passive"))
      (node (ref "IC3") (pin "4") (pinfunction "RF1_4") (pintype "bidirectional"))
    )
    (net (code "36") (name "Net-(IC3-RF2)") (class "Default")
      (node (ref "C36") (pin "1") (pinfunction "1_1") (pintype "passive"))
      (node (ref "IC3") (pin "15") (pinfunction "RF2_15") (pintype "bidirectional"))
    )
    (net (code "37") (name "Net-(IC3-VCC)") (class "Default")
      (node (ref "C13") (pin "2") (pinfunction "2_2") (pintype "passive"))
      (node (ref "C22") (pin "2") (pinfunction "2_2") (pintype "passive"))
      (node (ref "C23") (pin "2") (pinfunction "2_2") (pintype "passive"))
      (node (ref "C24") (pin "2") (pinfunction "2_2") (pintype "passive"))
      (node (ref "IC3") (pin "2") (pinfunction "VCC_2") (pintype "power_in"))
      (node (ref "L7") (pin "2") (pinfunction "2_2") (pintype "passive"))
    )
    (net (code "38") (name "Net-(IC7-EN)") (class "Default")
      (node (ref "IC7") (pin "5") (pinfunction "EN_5") (pintype "input"))
      (node (ref "R23") (pin "2") (pinfunction "2_2") (pintype "passive"))
    )
    (net (code "39") (name "Net-(IC7-RF1)") (class "Default")
      (node (ref "C47") (pin "1") (pinfunction "1_1") (pintype "passive"))
      (node (ref "IC7") (pin "9") (pinfunction "RF1_9") (pintype "bidirectional"))
    )
    (net (code "40") (name "Net-(IC7-RF2)") (class "Default")
      (node (ref "C49") (pin "1") (pinfunction "1_1") (pintype "passive"))
      (node (ref "IC7") (pin "12") (pinfunction "RF2_12") (pintype "bidirectional"))
    )
    (net (code "41") (name "Net-(IC7-RFC)") (class "Default")
      (node (ref "C36") (pin "2") (pinfunction "2_2") (pintype "passive"))
      (node (ref "IC7") (pin "3") (pinfunction "RFC_3") (pintype "bidirectional"))
    )
    (net (code "42") (name "Net-(IC7-VDD)") (class "Default")
      (node (ref "C38") (pin "1") (pinfunction "1_1") (pintype "passive"))
      (node (ref "C39") (pin "2") (pinfunction "2_2") (pintype "passive"))
      (node (ref "C40") (pin "2") (pinfunction "2_2") (pintype "passive"))
      (node (ref "IC7") (pin "1") (pinfunction "VDD_1") (pintype "power_in"))
      (node (ref "L6") (pin "1") (pinfunction "1_1") (pintype "passive"))
    )
    (net (code "43") (name "Net-(IC19-LE{slash}HYS)") (class "Default")
      (node (ref "IC19") (pin "8") (pinfunction "LE/HYS_8") (pintype "input"))
      (node (ref "R96") (pin "2") (pinfunction "2_2") (pintype "passive"))
    )
    (net (code "44") (name "Net-(IC19-VCCI)") (class "Default")
      (node (ref "C60") (pin "2") (pinfunction "2_2") (pintype "passive"))
      (node (ref "C61") (pin "2") (pinfunction "2_2") (pintype "passive"))
      (node (ref "IC19") (pin "2") (pinfunction "VCCI_2") (pintype "power_in"))
      (node (ref "L3") (pin "2") (pinfunction "2_2") (pintype "passive"))
      (node (ref "R91") (pin "1") (pinfunction "1_1") (pintype "passive"))
    )
    (net (code "45") (name "Net-(IC19-VCCO)") (class "Default")
      (node (ref "C62") (pin "2") (pinfunction "2_2") (pintype "passive"))
      (node (ref "IC19") (pin "1") (pinfunction "VCCO_1") (pintype "power_in"))
      (node (ref "L5") (pin "1") (pinfunction "1_1") (pintype "passive"))
    )
    (net (code "46") (name "Net-(IC19-VP)") (class "Default")
      (node (ref "C63") (pin "1") (pinfunction "1_1") (pintype "passive"))
      (node (ref "IC19") (pin "4") (pinfunction "VP_4") (pintype "input"))
      (node (ref "R93") (pin "1") (pinfunction "1_1") (pintype "passive"))
    )
    (net (code "47") (name "Net-(L1-Pad1)") (class "Default")
      (node (ref "L1") (pin "1") (pinfunction "1_1") (pintype "passive"))
      (node (ref "R36") (pin "2") (pinfunction "2_2") (pintype "passive"))
    )
    (net (code "48") (name "Net-(R21-Pad1)") (class "Default")
      (node (ref "R21") (pin "1") (pinfunction "1_1") (pintype "passive"))
      (node (ref "R35") (pin "2") (pinfunction "2_2") (pintype "passive"))
      (node (ref "R40") (pin "1") (pinfunction "1_1") (pintype "passive"))
      (node (ref "R47") (pin "2") (pinfunction "2_2") (pintype "passive"))
    )
    (net (code "49") (name "Net-(R21-Pad2)") (class "Default")
      (node (ref "R21") (pin "2") (pinfunction "2_2") (pintype "passive"))
      (node (ref "R34") (pin "2") (pinfunction "2_2") (pintype "passive"))
      (node (ref "R46") (pin "2") (pinfunction "2_2") (pintype "passive"))
      (node (ref "R50") (pin "2") (pinfunction "2_2") (pintype "passive"))
    )
    (net (code "50") (name "Net-(R22-Pad2)") (class "Default")
      (node (ref "R22") (pin "2") (pinfunction "2_2") (pintype "passive"))
      (node (ref "R37") (pin "1") (pinfunction "1_1") (pintype "passive"))
      (node (ref "R43") (pin "2") (pinfunction "2_2") (pintype "passive"))
      (node (ref "R48") (pin "1") (pinfunction "1_1") (pintype "passive"))
    )
    (net (code "51") (name "Net-(R24-Pad2)") (class "Default")
      (node (ref "R24") (pin "2") (pinfunction "2_2") (pintype "passive"))
      (node (ref "R44") (pin "2") (pinfunction "2_2") (pintype "passive"))
      (node (ref "R48") (pin "2") (pinfunction "2_2") (pintype "passive"))
      (node (ref "R49") (pin "1") (pinfunction "1_1") (pintype "passive"))
    )
    (net (code "52") (name "Net-(R33-Pad2)") (class "Default")
      (node (ref "R33") (pin "2") (pinfunction "2_2") (pintype "passive"))
      (node (ref "R45") (pin "2") (pinfunction "2_2") (pintype "passive"))
      (node (ref "R49") (pin "2") (pinfunction "2_2") (pintype "passive"))
      (node (ref "R50") (pin "1") (pinfunction "1_1") (pintype "passive"))
    )
    (net (code "53") (name "Net-(R38-Pad1)") (class "Default")
      (node (ref "R38") (pin "1") (pinfunction "1_1") (pintype "passive"))
      (node (ref "TR1") (pin "2") (pinfunction "P1_2") (pintype "passive"))
    )
    (net (code "54") (name "Net-(R41-Pad1)") (class "Default")
      (node (ref "R41") (pin "1") (pinfunction "1_1") (pintype "passive"))
      (node (ref "TR1") (pin "3") (pinfunction "P1_3") (pintype "passive"))
    )
    (net (code "55") (name "Net-(R91-Pad2)") (class "Default")
      (node (ref "R91") (pin "2") (pinfunction "2_2") (pintype "passive"))
      (node (ref "R92") (pin "2") (pinfunction "2_2") (pintype "passive"))
      (node (ref "R93") (pin "2") (pinfunction "2_2") (pintype "passive"))
      (node (ref "R94") (pin "2") (pinfunction "2_2") (pintype "passive"))
    )
    (net (code "56") (name "Net-(TR1-NC)") (class "Default")
      (node (ref "C30") (pin "2") (pinfunction "2_2") (pintype "passive"))
      (node (ref "TR1") (pin "5") (pinfunction "NC_5") (pintype "passive"))
    )
    (net (code "57") (name "P2V5") (class "Default")
      (node (ref "L5") (pin "2") (pinfunction "2_2") (pintype "passive"))
    )
    (net (code "58") (name "P5V0A") (class "Default")
      (node (ref "L3") (pin "1") (pinfunction "1_1") (pintype "passive"))
      (node (ref "L6") (pin "2") (pinfunction "2_2") (pintype "passive"))
      (node (ref "L7") (pin "1") (pinfunction "1_1") (pintype "passive"))
    )
    (net (code "59") (name "P11V5RF") (class "Default")
      (node (ref "C4") (pin "2") (pinfunction "2_2") (pintype "passive"))
      (node (ref "C5") (pin "2") (pinfunction "2_2") (pintype "passive"))
      (node (ref "R36") (pin "1") (pinfunction "1_1") (pintype "passive"))
    )
    (net (code "60") (name "unconnected-(IC7-NC-Pad4)") (class "Default")
      (node (ref "IC7") (pin "4") (pinfunction "NC_4") (pintype "passive"))
    )
    (net (code "61") (name "unconnected-(IC7-NC-Pad6)") (class "Default")
      (node (ref "IC7") (pin "6") (pinfunction "NC_6") (pintype "passive"))
    )
    (net (code "62") (name "unconnected-(IC7-NC-Pad7)") (class "Default")
      (node (ref "IC7") (pin "7") (pinfunction "NC_7") (pintype "passive"))
    )
    (net (code "63") (name "unconnected-(IC7-NC-Pad8)") (class "Default")
      (node (ref "IC7") (pin "8") (pinfunction "NC_8") (pintype "passive"))
    )
    (net (code "64") (name "unconnected-(IC7-NC-Pad13)") (class "Default")
      (node (ref "IC7") (pin "13") (pinfunction "NC_13") (pintype "passive"))
    )
    (net (code "65") (name "unconnected-(IC7-NC-Pad14)") (class "Default")
      (node (ref "IC7") (pin "14") (pinfunction "NC_14") (pintype "passive"))
    )
    (net (code "66") (name "unconnected-(IC7-NC-Pad15)") (class "Default")
      (node (ref "IC7") (pin "15") (pinfunction "NC_15") (pintype "passive"))
    )
    (net (code "67") (name "unconnected-(IC7-NC-Pad16)") (class "Default")
      (node (ref "IC7") (pin "16") (pinfunction "NC_16") (pintype "passive"))
    )
  )
)
